# RS485.net
KiCad netlist of a schematic drawn in Altium Designer
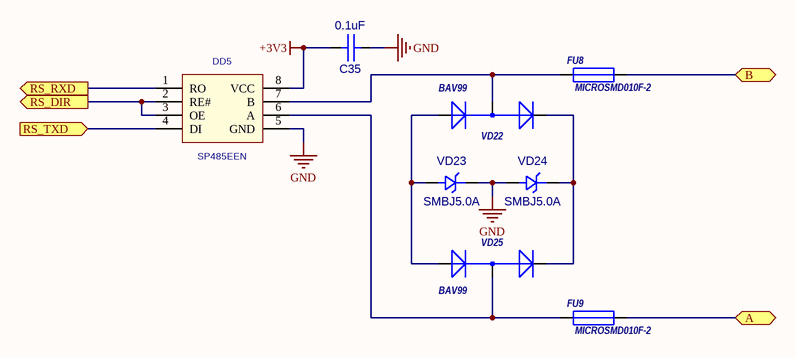
[diagram p0: RS485.SchDoc]

(export (version "E")
  (design (tool "Eeschema 10.0.6"))
  (components
    (comp (ref "C35")
      (value "0.1uF")
      (footprint "CC0603")
      (description "CC0603")
      (libsource (lib "gprs_modem_2") (part "CC0603"))
    )
    (comp (ref "DD5")
      (value "SP485EEN")
      (footprint "SO-8")
      (description "SP485")
      (libsource (lib "gprs_modem_2") (part "SP485"))
    )
    (comp (ref "FU8")
      (value "MICROSMD010F-2")
      (footprint "RC1210")
      (description "MICROSMD")
      (libsource (lib "gprs_modem_2") (part "MICROSMD"))
    )
    (comp (ref "FU9")
      (value "MICROSMD010F-2")
      (footprint "RC1210")
      (description "MICROSMD")
      (libsource (lib "gprs_modem_2") (part "MICROSMD"))
    )
    (comp (ref "VD22")
      (value "BAV99")
      (footprint "SOT-23(GSD)")
      (description "1.0 Ampere General Purpose Rectifier")
      (libsource (lib "gprs_modem_2") (part "BAV99"))
    )
    (comp (ref "VD23")
      (value "SMBJ5.0A")
      (footprint "SMB")
      (description "SMBJ")
      (libsource (lib "gprs_modem_2") (part "SMBJ"))
    )
    (comp (ref "VD24")
      (value "SMBJ5.0A")
      (footprint "SMB")
      (description "SMBJ")
      (libsource (lib "gprs_modem_2") (part "SMBJ"))
    )
    (comp (ref "VD25")
      (value "BAV99")
      (footprint "SOT-23(GSD)")
      (description "1.0 Ampere General Purpose Rectifier")
      (libsource (lib "gprs_modem_2") (part "BAV99"))
    )
  )
  (nets
    (net (code "1") (name "+3V3") (class "Default")
      (node (ref "C35") (pin "2") (pinfunction "B_2") (pintype "passive"))
      (node (ref "DD5") (pin "8") (pinfunction "VCC_8") (pintype "passive"))
    )
    (net (code "2") (name "/A") (class "Default") (node (ref "FU9") (pin "2") (pintype "passive")))
    (net (code "3") (name "/B") (class "Default") (node (ref "FU8") (pin "2") (pintype "passive")))
    (net (code "4") (name "/RS_DIR") (class "Default")
      (node (ref "DD5") (pin "2") (pinfunction "RE#_2") (pintype "passive"))
      (node (ref "DD5") (pin "3") (pinfunction "OE_3") (pintype "passive"))
    )
    (net (code "5") (name "/RS_RXD") (class "Default")
      (node (ref "DD5") (pin "1") (pinfunction "RO_1") (pintype "passive"))
    )
    (net (code "6") (name "/RS_TXD") (class "Default")
      (node (ref "DD5") (pin "4") (pinfunction "DI_4") (pintype "passive"))
    )
    (net (code "7") (name "GND") (class "Default")
      (node (ref "C35") (pin "1") (pinfunction "A_1") (pintype "passive"))
      (node (ref "DD5") (pin "5") (pinfunction "GND_5") (pintype "passive"))
      (node (ref "VD23") (pin "2") (pinfunction "K_2") (pintype "passive"))
      (node (ref "VD24") (pin "1") (pinfunction "A_1") (pintype "passive"))
    )
    (net (code "8") (name "Net-(DD5-A)") (class "Default")
      (node (ref "DD5") (pin "6") (pinfunction "A_6") (pintype "passive"))
      (node (ref "FU9") (pin "1") (pintype "passive"))
      (node (ref "VD25") (pin "3") (pinfunction "AK_3") (pintype "passive"))
    )
    (net (code "9") (name "Net-(DD5-B)") (class "Default")
      (node (ref "DD5") (pin "7") (pinfunction "B_7") (pintype "passive"))
      (node (ref "FU8") (pin "1") (pintype "passive"))
      (node (ref "VD22") (pin "3") (pinfunction "AK_3") (pintype "passive"))
    )
    (net (code "10") (name "Net-(VD22-A)") (class "Default")
      (node (ref "VD22") (pin "1") (pinfunction "A_1") (pintype "passive"))
      (node (ref "VD23") (pin "1") (pinfunction "A_1") (pintype "passive"))
      (node (ref "VD25") (pin "1") (pinfunction "A_1") (pintype "passive"))
    )
    (net (code "11") (name "Net-(VD22-K)") (class "Default")
      (node (ref "VD22") (pin "2") (pinfunction "K_2") (pintype "passive"))
      (node (ref "VD24") (pin "2") (pinfunction "K_2") (pintype "passive"))
      (node (ref "VD25") (pin "2") (pinfunction "K_2") (pintype "passive"))
    )
  )
)
